# power.net
KiCad netlist of a schematic drawn in EAGLE
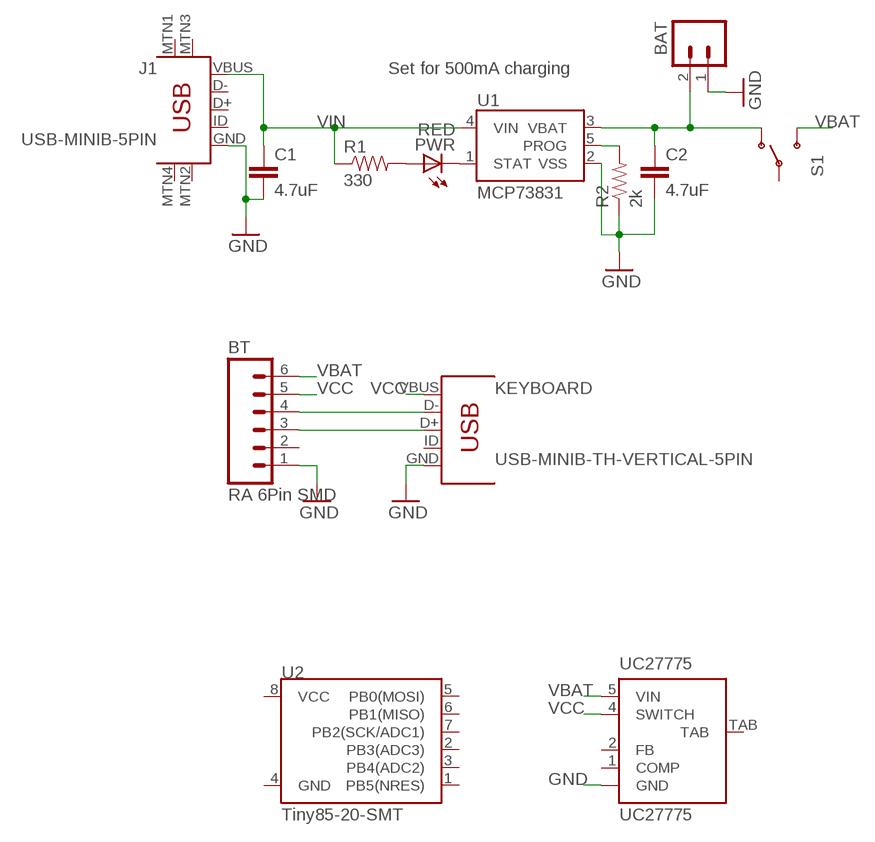
[diagram p0: schematic, sheet 1]

(export (version "E")
  (design (tool "Eeschema 10.0.6"))
  (components
    (comp (ref "BAT")
      (value "LiPo Battery")
      (footprint "eagle-import:JST-2-SMD")
      (libsource (lib "eagle-import") (part "M02-JST-2MM-SMT"))
    )
    (comp (ref "BT")
      (value "RA 6Pin SMD")
      (footprint "eagle-import:1X06-SMD-NOHOLES")
      (libsource (lib "eagle-import") (part "M06SMD-NOHOLES"))
    )
    (comp (ref "C1")
      (value "4.7uF")
      (footprint "eagle-import:0805-CAP")
      (libsource (lib "eagle-import") (part "1.0UF-25V-+80/-20(0805){dblquote}"))
    )
    (comp (ref "C2")
      (value "4.7uF")
      (footprint "eagle-import:0805-CAP")
      (libsource (lib "eagle-import") (part "1.0UF-25V-+80/-20(0805){dblquote}"))
    )
    (comp (ref "J1")
      (value "USB-MINIB-5PIN")
      (footprint "eagle-import:USB-MINIB")
      (libsource (lib "eagle-import") (part "USB-MINIB-5PIN"))
    )
    (comp (ref "KEYBOARD")
      (value "USB-MINIB-TH-VERTICAL-5PIN")
      (footprint "eagle-import:USB-MINIB-TH-VERTICAL")
      (libsource (lib "eagle-import") (part "USB-MINIB-TH-VERTICAL-5PIN"))
    )
    (comp (ref "PWR")
      (value "RED")
      (footprint "eagle-import:LED-0603")
      (libsource (lib "eagle-import") (part "LED0603"))
    )
    (comp (ref "R1")
      (value "330")
      (footprint "eagle-import:0805")
      (libsource (lib "eagle-import") (part "0.22OHM-1/4W-1%(0805)"))
    )
    (comp (ref "R2")
      (value "2k")
      (footprint "eagle-import:0805")
      (libsource (lib "eagle-import") (part "0.22OHM-1/4W-1%(0805)"))
    )
    (comp (ref "S1")
      (value "SWITCH-SPDT-SMD-A")
      (footprint "eagle-import:SWITCH-SPST-SMD-A")
      (libsource (lib "eagle-import") (part "SWITCH-SPDT-SMD-A"))
    )
    (comp (ref "U1")
      (value "MCP73831")
      (footprint "eagle-import:SOT23-5")
      (libsource (lib "eagle-import") (part "MCP73831"))
    )
    (comp (ref "U2")
      (value "Tiny85-20-SMT")
      (footprint "eagle-import:SO08-EIAJ")
      (libsource (lib "eagle-import") (part "ATTINY45TINY85-20-SMT"))
    )
    (comp (ref "UC27775")
      (value "UC27775")
      (footprint "eagle-import:TO263_5")
      (fields (field (name "MF") "TI"))
      (libsource (lib "eagle-import") (part "UC27775"))
    )
  )
  (nets
    (net (code "1") (name "/VBAT") (class "Default")
      (node (ref "BT") (pin "6") (pinfunction "6_6") (pintype "passive"))
      (node (ref "S1") (pin "3") (pinfunction "S_3") (pintype "passive"))
      (node (ref "UC27775") (pin "5") (pinfunction "VIN_5") (pintype "input"))
    )
    (net (code "2") (name "/VCC") (class "Default")
      (node (ref "BT") (pin "5") (pinfunction "5_5") (pintype "passive"))
      (node (ref "KEYBOARD") (pin "VBUS") (pinfunction "VBUS_VBUS") (pintype "bidirectional"))
      (node (ref "UC27775") (pin "4") (pinfunction "SWITCH_4") (pintype "output"))
    )
    (net (code "3") (name "/VIN") (class "Default")
      (node (ref "C1") (pin "1") (pinfunction "1_1") (pintype "passive"))
      (node (ref "J1") (pin "VBUS") (pinfunction "VBUS_VBUS") (pintype "bidirectional"))
      (node (ref "R1") (pin "1") (pinfunction "1_1") (pintype "passive"))
      (node (ref "U1") (pin "4") (pinfunction "VIN_4") (pintype "power_in"))
    )
    (net (code "4") (name "GND") (class "Default")
      (node (ref "BAT") (pin "1") (pinfunction "1_1") (pintype "passive"))
      (node (ref "BT") (pin "1") (pinfunction "1_1") (pintype "passive"))
      (node (ref "C1") (pin "2") (pinfunction "2_2") (pintype "passive"))
      (node (ref "C2") (pin "2") (pinfunction "2_2") (pintype "passive"))
      (node (ref "J1") (pin "GND") (pinfunction "GND_GND") (pintype "bidirectional"))
      (node (ref "KEYBOARD") (pin "GND") (pinfunction "GND_GND") (pintype "bidirectional"))
      (node (ref "R2") (pin "1") (pinfunction "1_1") (pintype "passive"))
      (node (ref "U1") (pin "2") (pinfunction "VSS_2") (pintype "power_in"))
      (node (ref "UC27775") (pin "3") (pinfunction "GND_3") (pintype "power_in"))
    )
    (net (code "5") (name "Net-(BT-Pad3)") (class "Default")
      (node (ref "BT") (pin "3") (pinfunction "3_3") (pintype "passive"))
      (node (ref "KEYBOARD") (pin "D+") (pinfunction "D+_D+") (pintype "bidirectional"))
    )
    (net (code "6") (name "Net-(BT-Pad4)") (class "Default")
      (node (ref "BT") (pin "4") (pinfunction "4_4") (pintype "passive"))
      (node (ref "KEYBOARD") (pin "D-") (pinfunction "D-_D-") (pintype "bidirectional"))
    )
    (net (code "7") (name "Net-(PWR-PadA)") (class "Default")
      (node (ref "PWR") (pin "A") (pinfunction "A_A") (pintype "passive"))
      (node (ref "R1") (pin "2") (pinfunction "2_2") (pintype "passive"))
    )
    (net (code "8") (name "Net-(S1-O)") (class "Default")
      (node (ref "BAT") (pin "2") (pinfunction "2_2") (pintype "passive"))
      (node (ref "C2") (pin "1") (pinfunction "1_1") (pintype "passive"))
      (node (ref "S1") (pin "1") (pinfunction "O_1") (pintype "passive"))
      (node (ref "U1") (pin "3") (pinfunction "VBAT_3") (pintype "power_in"))
    )
    (net (code "9") (name "Net-(U1-PROG)") (class "Default")
      (node (ref "R2") (pin "2") (pinfunction "2_2") (pintype "passive"))
      (node (ref "U1") (pin "5") (pinfunction "PROG_5") (pintype "input"))
    )
    (net (code "10") (name "Net-(U1-STAT)") (class "Default")
      (node (ref "PWR") (pin "C") (pinfunction "C_C") (pintype "passive"))
      (node (ref "U1") (pin "1") (pinfunction "STAT_1") (pintype "output"))
    )
    (net (code "11") (name "unconnected-(BT-Pad2)") (class "Default")
      (node (ref "BT") (pin "2") (pinfunction "2_2") (pintype "passive"))
    )
    (net (code "12") (name "unconnected-(J1-MTN1-PadMTN3)") (class "Default")
      (node (ref "J1") (pin "MTN3") (pinfunction "MTN1_MTN3") (pintype "bidirectional"))
    )
    (net (code "13") (name "unconnected-(J1-MTN2-PadMTN1)") (class "Default")
      (node (ref "J1") (pin "MTN1") (pinfunction "MTN2_MTN1") (pintype "bidirectional"))
    )
    (net (code "14") (name "unconnected-(J1-MTN3-PadMTN2)") (class "Default")
      (node (ref "J1") (pin "MTN2") (pinfunction "MTN3_MTN2") (pintype "bidirectional"))
    )
    (net (code "15") (name "unconnected-(J1-PadD+)") (class "Default")
      (node (ref "J1") (pin "D+") (pinfunction "D+_D+") (pintype "bidirectional"))
    )
    (net (code "16") (name "unconnected-(J1-PadD-)") (class "Default")
      (node (ref "J1") (pin "D-") (pinfunction "D-_D-") (pintype "bidirectional"))
    )
    (net (code "17") (name "unconnected-(J1-PadID)") (class "Default")
      (node (ref "J1") (pin "ID") (pinfunction "ID_ID") (pintype "bidirectional"))
    )
    (net (code "18") (name "unconnected-(J1-PadMTN4)") (class "Default")
      (node (ref "J1") (pin "MTN4") (pinfunction "MTN4_MTN4") (pintype "bidirectional"))
    )
    (net (code "19") (name "unconnected-(KEYBOARD-PadID)") (class "Default")
      (node (ref "KEYBOARD") (pin "ID") (pinfunction "ID_ID") (pintype "bidirectional"))
    )
    (net (code "20") (name "unconnected-(S1-P-Pad2)") (class "Default")
      (node (ref "S1") (pin "2") (pinfunction "P_2") (pintype "passive"))
    )
    (net (code "21") (name "unconnected-(U2-GND-Pad4)") (class "Default")
      (node (ref "U2") (pin "4") (pinfunction "GND_4") (pintype "bidirectional"))
    )
    (net (code "22") (name "unconnected-(U2-PB0(MOSI)-Pad5)") (class "Default")
      (node (ref "U2") (pin "5") (pinfunction "PB0(MOSI)_5") (pintype "bidirectional"))
    )
    (net (code "23") (name "unconnected-(U2-PB1(MISO)-Pad6)") (class "Default")
      (node (ref "U2") (pin "6") (pinfunction "PB1(MISO)_6") (pintype "bidirectional"))
    )
    (net (code "24") (name "unconnected-(U2-PB2(SCK{slash}ADC1)-Pad7)") (class "Default")
      (node (ref "U2") (pin "7") (pinfunction "PB2(SCK/ADC1)_7") (pintype "bidirectional"))
    )
    (net (code "25") (name "unconnected-(U2-PB3(ADC3)-Pad2)") (class "Default")
      (node (ref "U2") (pin "2") (pinfunction "PB3(ADC3)_2") (pintype "bidirectional"))
    )
    (net (code "26") (name "unconnected-(U2-PB4(ADC2)-Pad3)") (class "Default")
      (node (ref "U2") (pin "3") (pinfunction "PB4(ADC2)_3") (pintype "bidirectional"))
    )
    (net (code "27") (name "unconnected-(U2-PB5(NRES)-Pad1)") (class "Default")
      (node (ref "U2") (pin "1") (pinfunction "PB5(NRES)_1") (pintype "bidirectional"))
    )
    (net (code "28") (name "unconnected-(U2-VCC-Pad8)") (class "Default")
      (node (ref "U2") (pin "8") (pinfunction "VCC_8") (pintype "bidirectional"))
    )
    (net (code "29") (name "unconnected-(UC27775-COMP-Pad1)") (class "Default")
      (node (ref "UC27775") (pin "1") (pinfunction "COMP_1") (pintype "input"))
    )
    (net (code "30") (name "unconnected-(UC27775-FB-Pad2)") (class "Default")
      (node (ref "UC27775") (pin "2") (pinfunction "FB_2") (pintype "input"))
    )
    (net (code "31") (name "unconnected-(UC27775-PadTAB)") (class "Default")
      (node (ref "UC27775") (pin "TAB") (pinfunction "TAB_TAB") (pintype "passive"))
    )
  )
)
